# takpad6_2.net
KiCad netlist of a schematic drawn in EAGLE
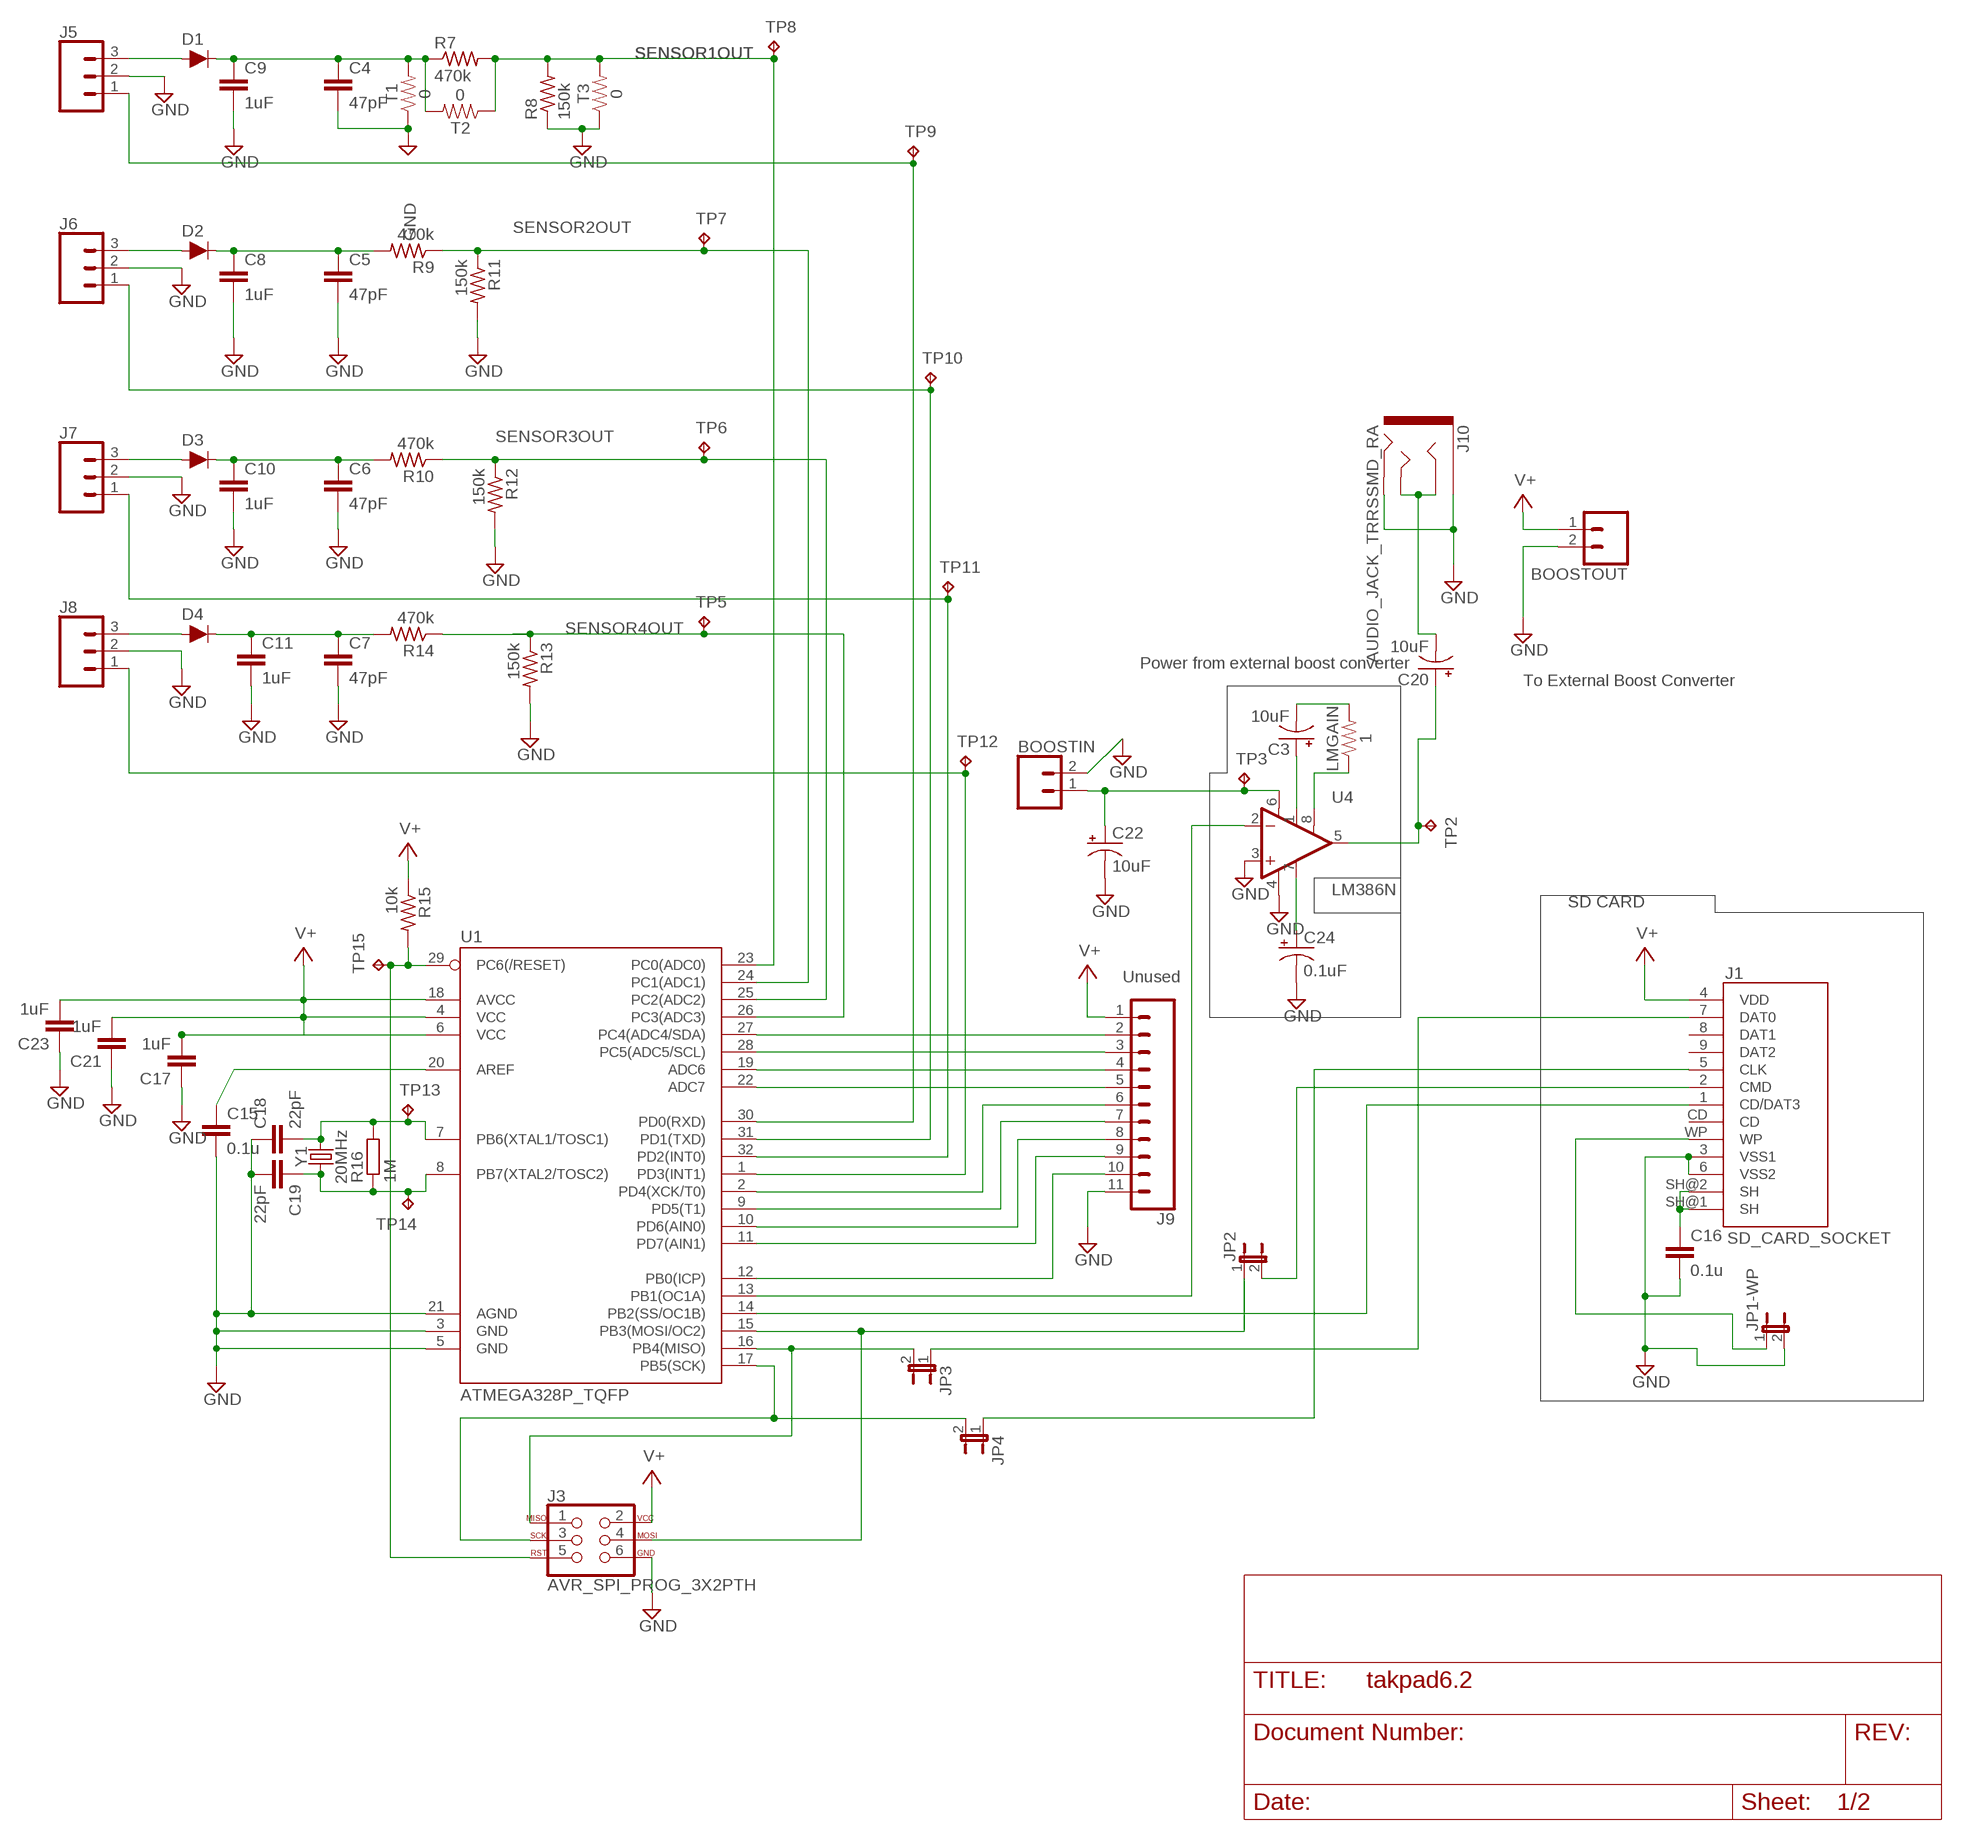
[diagram p0: schematic, sheet 1]
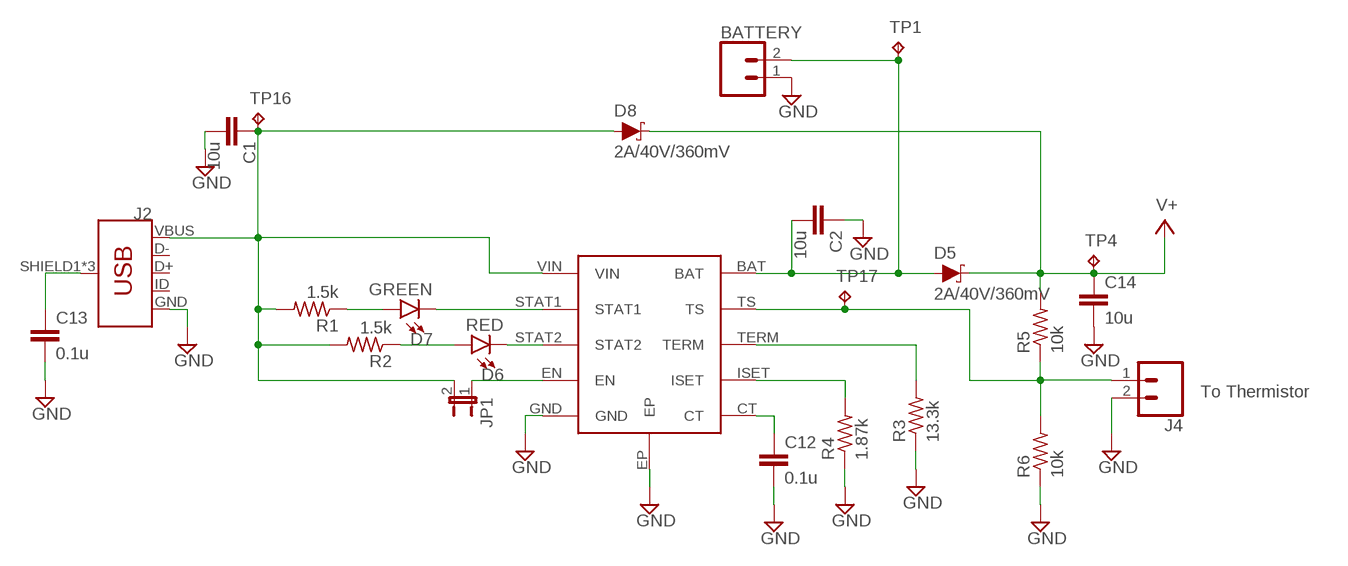
[diagram p1: schematic, sheet 2]

(export (version "E")
  (design (tool "Eeschema 10.0.6"))
  (components
    (comp (ref "BOOSTIN")
      (value "CONN_02")
      (footprint "eagle-import:1X02")
      (libsource (lib "eagle-import") (part "CONN_02"))
    )
    (comp (ref "BOOSTOUT")
      (value "CONN_02")
      (footprint "eagle-import:1X02")
      (libsource (lib "eagle-import") (part "CONN_02"))
    )
    (comp (ref "C3")
      (value "10uF")
      (footprint "eagle-import:CPOL-RADIAL-2.5MM-5MM-KIT")
      (libsource (lib "eagle-import") (part "10UF-POLAR-RADIAL-2.5MM-KIT-25V-20%"))
    )
    (comp (ref "C4")
      (value "47pF")
      (footprint "eagle-import:0603")
      (libsource (lib "eagle-import") (part "47PF-0603-50V-5%"))
    )
    (comp (ref "C5")
      (value "47pF")
      (footprint "eagle-import:0603")
      (libsource (lib "eagle-import") (part "47PF-0603-50V-5%"))
    )
    (comp (ref "C6")
      (value "47pF")
      (footprint "eagle-import:0603")
      (libsource (lib "eagle-import") (part "47PF-0603-50V-5%"))
    )
    (comp (ref "C7")
      (value "47pF")
      (footprint "eagle-import:0603")
      (libsource (lib "eagle-import") (part "47PF-0603-50V-5%"))
    )
    (comp (ref "C8")
      (value "1uF")
      (footprint "eagle-import:0603")
      (libsource (lib "eagle-import") (part "47PF-0603-50V-5%"))
    )
    (comp (ref "C9")
      (value "1uF")
      (footprint "eagle-import:0603")
      (libsource (lib "eagle-import") (part "47PF-0603-50V-5%"))
    )
    (comp (ref "C10")
      (value "1uF")
      (footprint "eagle-import:0603")
      (libsource (lib "eagle-import") (part "47PF-0603-50V-5%"))
    )
    (comp (ref "C11")
      (value "1uF")
      (footprint "eagle-import:0603")
      (libsource (lib "eagle-import") (part "47PF-0603-50V-5%"))
    )
    (comp (ref "C15")
      (value "0.1u")
      (footprint "eagle-import:C0402")
      (libsource (lib "eagle-import") (part "C-EUC0402"))
    )
    (comp (ref "C16")
      (value "0.1u")
      (footprint "eagle-import:C0402")
      (libsource (lib "eagle-import") (part "C-EUC0402"))
    )
    (comp (ref "C17")
      (value "1uF")
      (footprint "eagle-import:0603")
      (libsource (lib "eagle-import") (part "47PF-0603-50V-5%"))
    )
    (comp (ref "C18")
      (value "22pF")
      (footprint "eagle-import:C0402")
      (libsource (lib "eagle-import") (part "resistor_348_C-EUC0402"))
    )
    (comp (ref "C19")
      (value "22pF")
      (footprint "eagle-import:C0402")
      (libsource (lib "eagle-import") (part "resistor_348_C-EUC0402"))
    )
    (comp (ref "C20")
      (value "10uF")
      (footprint "eagle-import:CPOL-RADIAL-2.5MM-5MM-KIT")
      (libsource (lib "eagle-import") (part "10UF-POLAR-RADIAL-2.5MM-KIT-25V-20%"))
    )
    (comp (ref "C21")
      (value "1uF")
      (footprint "eagle-import:0603")
      (libsource (lib "eagle-import") (part "47PF-0603-50V-5%"))
    )
    (comp (ref "C22")
      (value "10uF")
      (footprint "eagle-import:CPOL-RADIAL-2.5MM-5MM-KIT")
      (libsource (lib "eagle-import") (part "10UF-POLAR-RADIAL-2.5MM-KIT-25V-20%"))
    )
    (comp (ref "C23")
      (value "1uF")
      (footprint "eagle-import:0603")
      (libsource (lib "eagle-import") (part "47PF-0603-50V-5%"))
    )
    (comp (ref "C24")
      (value "0.1uF")
      (footprint "eagle-import:CPOL-RADIAL-2.5MM-5MM-KIT")
      (libsource (lib "eagle-import") (part "10UF-POLAR-RADIAL-2.5MM-KIT-25V-20%"))
    )
    (comp (ref "D1")
      (value "200mA/100V/1V")
      (footprint "eagle-import:DIODE-1N4148")
      (libsource (lib "eagle-import") (part "DIODE-1N4148"))
    )
    (comp (ref "D2")
      (value "200mA/100V/1V")
      (footprint "eagle-import:DIODE-1N4148")
      (libsource (lib "eagle-import") (part "DIODE-1N4148"))
    )
    (comp (ref "D3")
      (value "200mA/100V/1V")
      (footprint "eagle-import:DIODE-1N4148")
      (libsource (lib "eagle-import") (part "DIODE-1N4148"))
    )
    (comp (ref "D4")
      (value "200mA/100V/1V")
      (footprint "eagle-import:DIODE-1N4148")
      (libsource (lib "eagle-import") (part "DIODE-1N4148"))
    )
    (comp (ref "J1")
      (value "SD_CARD_SOCKET")
      (footprint "eagle-import:SD")
      (libsource (lib "eagle-import") (part "SD_CARD_SOCKET"))
    )
    (comp (ref "J3")
      (value "AVR_SPI_PROG_3X2PTH")
      (footprint "eagle-import:2X3")
      (libsource (lib "eagle-import") (part "AVR_SPI_PROG_3X2PTH"))
    )
    (comp (ref "J5")
      (value "CONN_03")
      (footprint "eagle-import:1X03")
      (libsource (lib "eagle-import") (part "CONN_03"))
    )
    (comp (ref "J6")
      (value "CONN_03")
      (footprint "eagle-import:1X03")
      (libsource (lib "eagle-import") (part "CONN_03"))
    )
    (comp (ref "J7")
      (value "CONN_03")
      (footprint "eagle-import:1X03")
      (libsource (lib "eagle-import") (part "CONN_03"))
    )
    (comp (ref "J8")
      (value "CONN_03")
      (footprint "eagle-import:1X03")
      (libsource (lib "eagle-import") (part "CONN_03"))
    )
    (comp (ref "J9")
      (value "CONN_11")
      (footprint "eagle-import:1X11")
      (libsource (lib "eagle-import") (part "CONN_11"))
    )
    (comp (ref "J10")
      (value "AUDIO_JACK_TRRSSMD_RA")
      (footprint "eagle-import:AUDIO_JACK_3.5MM_TRRS_SMD_RA")
      (libsource (lib "eagle-import") (part "AUDIO_JACK_TRRSSMD_RA"))
    )
    (comp (ref "JP1-WP")
      (value "JUMPER-2PTH")
      (footprint "eagle-import:1X02")
      (libsource (lib "eagle-import") (part "JUMPER-2PTH"))
    )
    (comp (ref "JP2")
      (value "JUMPER-2PTH")
      (footprint "eagle-import:1X02")
      (libsource (lib "eagle-import") (part "JUMPER-2PTH"))
    )
    (comp (ref "JP3")
      (value "JUMPER-2PTH")
      (footprint "eagle-import:1X02")
      (libsource (lib "eagle-import") (part "JUMPER-2PTH"))
    )
    (comp (ref "JP4")
      (value "JUMPER-2PTH")
      (footprint "eagle-import:1X02")
      (libsource (lib "eagle-import") (part "JUMPER-2PTH"))
    )
    (comp (ref "LMGAIN")
      (value "1")
      (footprint "eagle-import:0603")
      (libsource (lib "eagle-import") (part "1OHM-0603-1/10W-1%"))
    )
    (comp (ref "R7")
      (value "470k")
      (footprint "eagle-import:M1206")
      (libsource (lib "eagle-import") (part "R-US_M1206"))
    )
    (comp (ref "R8")
      (value "150k")
      (footprint "eagle-import:M1206")
      (libsource (lib "eagle-import") (part "R-US_M1206"))
    )
    (comp (ref "R9")
      (value "470k")
      (footprint "eagle-import:M1206")
      (libsource (lib "eagle-import") (part "R-US_M1206"))
    )
    (comp (ref "R10")
      (value "470k")
      (footprint "eagle-import:M1206")
      (libsource (lib "eagle-import") (part "R-US_M1206"))
    )
    (comp (ref "R11")
      (value "150k")
      (footprint "eagle-import:M1206")
      (libsource (lib "eagle-import") (part "R-US_M1206"))
    )
    (comp (ref "R12")
      (value "150k")
      (footprint "eagle-import:M1206")
      (libsource (lib "eagle-import") (part "R-US_M1206"))
    )
    (comp (ref "R13")
      (value "150k")
      (footprint "eagle-import:M1206")
      (libsource (lib "eagle-import") (part "R-US_M1206"))
    )
    (comp (ref "R14")
      (value "470k")
      (footprint "eagle-import:M1206")
      (libsource (lib "eagle-import") (part "R-US_M1206"))
    )
    (comp (ref "R15")
      (value "10k")
      (footprint "eagle-import:M1206")
      (libsource (lib "eagle-import") (part "R-US_M1206"))
    )
    (comp (ref "R16")
      (value "1M")
      (footprint "eagle-import:R0402")
      (libsource (lib "eagle-import") (part "R-EU_R0402"))
    )
    (comp (ref "T1")
      (value "0")
      (footprint "eagle-import:AXIAL-0.3")
      (libsource (lib "eagle-import") (part "1KOHM-HORIZ-1/4W-1%"))
    )
    (comp (ref "T2")
      (value "0")
      (footprint "eagle-import:AXIAL-0.3")
      (libsource (lib "eagle-import") (part "1KOHM-HORIZ-1/4W-1%"))
    )
    (comp (ref "T3")
      (value "0")
      (footprint "eagle-import:AXIAL-0.3")
      (libsource (lib "eagle-import") (part "1KOHM-HORIZ-1/4W-1%"))
    )
    (comp (ref "TP2")
      (value "TPB1,27")
      (footprint "eagle-import:B1,27")
      (libsource (lib "eagle-import") (part "TPB1,27"))
    )
    (comp (ref "TP3")
      (value "TPB1,27")
      (footprint "eagle-import:B1,27")
      (libsource (lib "eagle-import") (part "TPB1,27"))
    )
    (comp (ref "TP5")
      (value "TPB1,27")
      (footprint "eagle-import:B1,27")
      (libsource (lib "eagle-import") (part "TPB1,27"))
    )
    (comp (ref "TP6")
      (value "TPB1,27")
      (footprint "eagle-import:B1,27")
      (libsource (lib "eagle-import") (part "TPB1,27"))
    )
    (comp (ref "TP7")
      (value "TPB1,27")
      (footprint "eagle-import:B1,27")
      (libsource (lib "eagle-import") (part "TPB1,27"))
    )
    (comp (ref "TP8")
      (value "TPB1,27")
      (footprint "eagle-import:B1,27")
      (libsource (lib "eagle-import") (part "TPB1,27"))
    )
    (comp (ref "TP9")
      (value "TPB1,27")
      (footprint "eagle-import:B1,27")
      (libsource (lib "eagle-import") (part "TPB1,27"))
    )
    (comp (ref "TP10")
      (value "TPB1,27")
      (footprint "eagle-import:B1,27")
      (libsource (lib "eagle-import") (part "TPB1,27"))
    )
    (comp (ref "TP11")
      (value "TPB1,27")
      (footprint "eagle-import:B1,27")
      (libsource (lib "eagle-import") (part "TPB1,27"))
    )
    (comp (ref "TP12")
      (value "TPB1,27")
      (footprint "eagle-import:B1,27")
      (libsource (lib "eagle-import") (part "TPB1,27"))
    )
    (comp (ref "TP13")
      (value "TPB1,27")
      (footprint "eagle-import:B1,27")
      (libsource (lib "eagle-import") (part "TPB1,27"))
    )
    (comp (ref "TP14")
      (value "TPB1,27")
      (footprint "eagle-import:B1,27")
      (libsource (lib "eagle-import") (part "TPB1,27"))
    )
    (comp (ref "TP15")
      (value "TPB1,27")
      (footprint "eagle-import:B1,27")
      (libsource (lib "eagle-import") (part "TPB1,27"))
    )
    (comp (ref "U1")
      (value "ATMEGA328P_TQFP")
      (footprint "eagle-import:TQFP32-08")
      (libsource (lib "eagle-import") (part "ATMEGA328P_TQFP"))
    )
    (comp (ref "U4")
      (value "LM386N")
      (footprint "eagle-import:DIP08")
      (libsource (lib "eagle-import") (part "LM386"))
    )
    (comp (ref "Y1")
      (value "20MHz")
      (footprint "eagle-import:HC49US")
      (libsource (lib "eagle-import") (part "CRYSTAL-16MHZPTH-HC49US"))
    )
    (comp (ref "BATTERY")
      (value "CONN_02")
      (footprint "eagle-import:1X02")
      (libsource (lib "eagle-import") (part "CONN_02"))
    )
    (comp (ref "C1")
      (value "10u")
      (footprint "eagle-import:C0402")
      (libsource (lib "eagle-import") (part "C-EUC0402"))
    )
    (comp (ref "C2")
      (value "10u")
      (footprint "eagle-import:C0402")
      (libsource (lib "eagle-import") (part "C-EUC0402"))
    )
    (comp (ref "C12")
      (value "0.1u")
      (footprint "eagle-import:C0402")
      (libsource (lib "eagle-import") (part "C-EUC0402"))
    )
    (comp (ref "C13")
      (value "0.1u")
      (footprint "eagle-import:C0402")
      (libsource (lib "eagle-import") (part "C-EUC0402"))
    )
    (comp (ref "C14")
      (value "10u")
      (footprint "eagle-import:C0402")
      (libsource (lib "eagle-import") (part "C-EUC0402"))
    )
    (comp (ref "D5")
      (value "2A/40V/360mV")
      (footprint "eagle-import:SMA-DIODE")
      (libsource (lib "eagle-import") (part "DIODE-SCHOTTKY-B340A"))
    )
    (comp (ref "D6")
      (value "RED")
      (footprint "eagle-import:LED-1206")
      (libsource (lib "eagle-import") (part "LED-RED1206"))
    )
    (comp (ref "D7")
      (value "GREEN")
      (footprint "eagle-import:LED-1206")
      (libsource (lib "eagle-import") (part "LED-GREEN1206"))
    )
    (comp (ref "D8")
      (value "2A/40V/360mV")
      (footprint "eagle-import:SMA-DIODE")
      (libsource (lib "eagle-import") (part "DIODE-SCHOTTKY-B340A"))
    )
    (comp (ref "J2")
      (value "USB_MICRO-BREDUCED_PASTE")
      (footprint "eagle-import:USB-B-MICRO-SMD_RED_PASTE")
      (libsource (lib "eagle-import") (part "USB_MICRO-BREDUCED_PASTE"))
    )
    (comp (ref "J4")
      (value "CONN_02")
      (footprint "eagle-import:1X02")
      (libsource (lib "eagle-import") (part "CONN_02"))
    )
    (comp (ref "JP1")
      (value "JUMPER-2PTH")
      (footprint "eagle-import:1X02")
      (libsource (lib "eagle-import") (part "JUMPER-2PTH"))
    )
    (comp (ref "R1")
      (value "1.5k")
      (footprint "eagle-import:M1206")
      (libsource (lib "eagle-import") (part "R-US_M1206"))
    )
    (comp (ref "R2")
      (value "1.5k")
      (footprint "eagle-import:M1206")
      (libsource (lib "eagle-import") (part "R-US_M1206"))
    )
    (comp (ref "R3")
      (value "13.3k")
      (footprint "eagle-import:M1206")
      (libsource (lib "eagle-import") (part "R-US_M1206"))
    )
    (comp (ref "R4")
      (value "1.87k")
      (footprint "eagle-import:M1206")
      (libsource (lib "eagle-import") (part "R-US_M1206"))
    )
    (comp (ref "R5")
      (value "10k")
      (footprint "eagle-import:M1206")
      (libsource (lib "eagle-import") (part "R-US_M1206"))
    )
    (comp (ref "R6")
      (value "10k")
      (footprint "eagle-import:M1206")
      (libsource (lib "eagle-import") (part "R-US_M1206"))
    )
    (comp (ref "TP1")
      (value "TPB1,27")
      (footprint "eagle-import:B1,27")
      (libsource (lib "eagle-import") (part "TPB1,27"))
    )
    (comp (ref "TP4")
      (value "TPB1,27")
      (footprint "eagle-import:B1,27")
      (libsource (lib "eagle-import") (part "TPB1,27"))
    )
    (comp (ref "TP16")
      (value "TPB1,27")
      (footprint "eagle-import:B1,27")
      (libsource (lib "eagle-import") (part "TPB1,27"))
    )
    (comp (ref "TP17")
      (value "TPB1,27")
      (footprint "eagle-import:B1,27")
      (libsource (lib "eagle-import") (part "TPB1,27"))
    )
    (comp (ref "U$1")
      (value "AAT3693")
      (footprint "eagle-import:IDH-AA-T1")
      (libsource (lib "eagle-import") (part "AAT3693"))
    )
  )
  (nets
    (net (code "1") (name "GND") (class "Default")
      (node (ref "BATTERY") (pin "1") (pinfunction "1_1") (pintype "passive"))
      (node (ref "BOOSTIN") (pin "2") (pinfunction "2_2") (pintype "passive"))
      (node (ref "BOOSTOUT") (pin "2") (pinfunction "2_2") (pintype "passive"))
      (node (ref "C1") (pin "2") (pinfunction "2_2") (pintype "passive"))
      (node (ref "C10") (pin "2") (pinfunction "2_2") (pintype "passive"))
      (node (ref "C11") (pin "2") (pinfunction "2_2") (pintype "passive"))
      (node (ref "C12") (pin "2") (pinfunction "2_2") (pintype "passive"))
      (node (ref "C13") (pin "2") (pinfunction "2_2") (pintype "passive"))
      (node (ref "C14") (pin "2") (pinfunction "2_2") (pintype "passive"))
      (node (ref "C15") (pin "2") (pinfunction "2_2") (pintype "passive"))
      (node (ref "C16") (pin "2") (pinfunction "2_2") (pintype "passive"))
      (node (ref "C17") (pin "1") (pinfunction "1_1") (pintype "passive"))
      (node (ref "C18") (pin "1") (pinfunction "1_1") (pintype "passive"))
      (node (ref "C19") (pin "2") (pinfunction "2_2") (pintype "passive"))
      (node (ref "C2") (pin "1") (pinfunction "1_1") (pintype "passive"))
      (node (ref "C21") (pin "1") (pinfunction "1_1") (pintype "passive"))
      (node (ref "C22") (pin "2") (pinfunction "-_2") (pintype "passive"))
      (node (ref "C23") (pin "1") (pinfunction "1_1") (pintype "passive"))
      (node (ref "C24") (pin "2") (pinfunction "-_2") (pintype "passive"))
      (node (ref "C4") (pin "2") (pinfunction "2_2") (pintype "passive"))
      (node (ref "C5") (pin "2") (pinfunction "2_2") (pintype "passive"))
      (node (ref "C6") (pin "2") (pinfunction "2_2") (pintype "passive"))
      (node (ref "C7") (pin "2") (pinfunction "2_2") (pintype "passive"))
      (node (ref "C8") (pin "2") (pinfunction "2_2") (pintype "passive"))
      (node (ref "C9") (pin "2") (pinfunction "2_2") (pintype "passive"))
      (node (ref "J1") (pin "3") (pinfunction "VSS1_3") (pintype "power_in"))
      (node (ref "J1") (pin "6") (pinfunction "VSS2_6") (pintype "power_in"))
      (node (ref "J10") (pin "EARTH") (pinfunction "EARTH_EARTH") (pintype "bidirectional"))
      (node (ref "J10") (pin "RING2") (pinfunction "RING2_RING2") (pintype "bidirectional"))
      (node (ref "J2") (pin "GND") (pinfunction "GND_GND") (pintype "power_in"))
      (node (ref "J3") (pin "6") (pinfunction "6_6") (pintype "passive"))
      (node (ref "J4") (pin "2") (pinfunction "2_2") (pintype "passive"))
      (node (ref "J5") (pin "2") (pinfunction "2_2") (pintype "passive"))
      (node (ref "J6") (pin "2") (pinfunction "2_2") (pintype "passive"))
      (node (ref "J7") (pin "2") (pinfunction "2_2") (pintype "passive"))
      (node (ref "J8") (pin "2") (pinfunction "2_2") (pintype "passive"))
      (node (ref "J9") (pin "11") (pinfunction "11_11") (pintype "passive"))
      (node (ref "JP1-WP") (pin "2") (pinfunction "2_2") (pintype "passive"))
      (node (ref "R11") (pin "2") (pinfunction "2_2") (pintype "passive"))
      (node (ref "R12") (pin "2") (pinfunction "2_2") (pintype "passive"))
      (node (ref "R13") (pin "2") (pinfunction "2_2") (pintype "passive"))
      (node (ref "R3") (pin "1") (pinfunction "1_1") (pintype "passive"))
      (node (ref "R4") (pin "1") (pinfunction "1_1") (pintype "passive"))
      (node (ref "R6") (pin "1") (pinfunction "1_1") (pintype "passive"))
      (node (ref "R8") (pin "1") (pinfunction "1_1") (pintype "passive"))
      (node (ref "T1") (pin "P$1") (pinfunction "1_P$1") (pintype "passive"))
      (node (ref "T3") (pin "P$1") (pinfunction "1_P$1") (pintype "passive"))
      (node (ref "U$1") (pin "EP") (pinfunction "EP_EP") (pintype "bidirectional"))
      (node (ref "U$1") (pin "GND") (pinfunction "GND_GND") (pintype "bidirectional"))
      (node (ref "U1") (pin "21") (pinfunction "AGND_21") (pintype "bidirectional"))
      (node (ref "U1") (pin "3") (pinfunction "GND_3") (pintype "bidirectional"))
      (node (ref "U1") (pin "5") (pinfunction "GND_5") (pintype "bidirectional"))
      (node (ref "U4") (pin "3") (pinfunction "+IN_3") (pintype "input"))
      (node (ref "U4") (pin "4") (pinfunction "V-_4") (pintype "power_in"))
    )
    (net (code "2") (name "Net-(BATTERY-Pad2)") (class "Default")
      (node (ref "BATTERY") (pin "2") (pinfunction "2_2") (pintype "passive"))
      (node (ref "C2") (pin "2") (pinfunction "2_2") (pintype "passive"))
      (node (ref "D5") (pin "A") (pinfunction "A_A") (pintype "passive"))
      (node (ref "TP1") (pin "TP") (pinfunction "TP_TP") (pintype "input"))
      (node (ref "U$1") (pin "BAT") (pinfunction "BAT_BAT") (pintype "bidirectional"))
    )
    (net (code "3") (name "Net-(C1-Pad1)") (class "Default")
      (node (ref "C1") (pin "1") (pinfunction "1_1") (pintype "passive"))
      (node (ref "D8") (pin "A") (pinfunction "A_A") (pintype "passive"))
      (node (ref "J2") (pin "VBUS") (pinfunction "VBUS_VBUS") (pintype "power_in"))
      (node (ref "JP1") (pin "2") (pinfunction "2_2") (pintype "passive"))
      (node (ref "R1") (pin "2") (pinfunction "2_2") (pintype "passive"))
      (node (ref "R2") (pin "2") (pinfunction "2_2") (pintype "passive"))
      (node (ref "TP16") (pin "TP") (pinfunction "TP_TP") (pintype "input"))
      (node (ref "U$1") (pin "VIN") (pinfunction "VIN_VIN") (pintype "bidirectional"))
    )
    (net (code "4") (name "Net-(C3-+)") (class "Default")
      (node (ref "C3") (pin "1") (pinfunction "+_1") (pintype "passive"))
      (node (ref "U4") (pin "1") (pinfunction "GAIN_1") (pintype "bidirectional"))
    )
    (net (code "5") (name "Net-(C3--)") (class "Default")
      (node (ref "C3") (pin "2") (pinfunction "-_2") (pintype "passive"))
      (node (ref "LMGAIN") (pin "2") (pinfunction "2_2") (pintype "passive"))
    )
    (net (code "6") (name "Net-(C5-Pad1)") (class "Default")
      (node (ref "C5") (pin "1") (pinfunction "1_1") (pintype "passive"))
      (node (ref "C8") (pin "1") (pinfunction "1_1") (pintype "passive"))
      (node (ref "D2") (pin "C") (pinfunction "C_C") (pintype "passive"))
      (node (ref "R9") (pin "2") (pinfunction "2_2") (pintype "passive"))
    )
    (net (code "7") (name "Net-(C10-Pad1)") (class "Default")
      (node (ref "C10") (pin "1") (pinfunction "1_1") (pintype "passive"))
      (node (ref "C6") (pin "1") (pinfunction "1_1") (pintype "passive"))
      (node (ref "D3") (pin "C") (pinfunction "C_C") (pintype "passive"))
      (node (ref "R10") (pin "2") (pinfunction "2_2") (pintype "passive"))
    )
    (net (code "8") (name "Net-(C11-Pad1)") (class "Default")
      (node (ref "C11") (pin "1") (pinfunction "1_1") (pintype "passive"))
      (node (ref "C7") (pin "1") (pinfunction "1_1") (pintype "passive"))
      (node (ref "D4") (pin "C") (pinfunction "C_C") (pintype "passive"))
      (node (ref "R14") (pin "2") (pinfunction "2_2") (pintype "passive"))
    )
    (net (code "9") (name "Net-(C12-Pad1)") (class "Default")
      (node (ref "C12") (pin "1") (pinfunction "1_1") (pintype "passive"))
      (node (ref "U$1") (pin "CT") (pinfunction "CT_CT") (pintype "bidirectional"))
    )
    (net (code "10") (name "Net-(C13-Pad1)") (class "Default")
      (node (ref "C13") (pin "1") (pinfunction "1_1") (pintype "passive"))
      (node (ref "J2") (pin "SHIELD1") (pinfunction "SHIELD_SHIELD1") (pintype "bidirectional"))
      (node (ref "J2") (pin "SHIELD2") (pinfunction "SHIELD_SHIELD2") (pintype "bidirectional"))
      (node (ref "J2") (pin "SHIELD3") (pinfunction "SHIELD_SHIELD3") (pintype "bidirectional"))
    )
    (net (code "11") (name "Net-(C16-Pad1)") (class "Default")
      (node (ref "C16") (pin "1") (pinfunction "1_1") (pintype "passive"))
      (node (ref "J1") (pin "SH@1") (pinfunction "SH_SH@1") (pintype "bidirectional"))
      (node (ref "J1") (pin "SH@2") (pinfunction "SH_SH@2") (pintype "bidirectional"))
    )
    (net (code "12") (name "Net-(C20-+)") (class "Default")
      (node (ref "C20") (pin "1") (pinfunction "+_1") (pintype "passive"))
      (node (ref "TP2") (pin "TP") (pinfunction "TP_TP") (pintype "input"))
      (node (ref "U4") (pin "5") (pinfunction "OUT_5") (pintype "output"))
    )
    (net (code "13") (name "Net-(C20--)") (class "Default")
      (node (ref "C20") (pin "2") (pinfunction "-_2") (pintype "passive"))
      (node (ref "J10") (pin "RING1") (pinfunction "RING1_RING1") (pintype "bidirectional"))
      (node (ref "J10") (pin "TIP") (pinfunction "TIP_TIP") (pintype "bidirectional"))
    )
    (net (code "14") (name "Net-(C22-+)") (class "Default")
      (node (ref "BOOSTIN") (pin "1") (pinfunction "1_1") (pintype "passive"))
      (node (ref "C22") (pin "1") (pinfunction "+_1") (pintype "passive"))
      (node (ref "TP3") (pin "TP") (pinfunction "TP_TP") (pintype "input"))
      (node (ref "U4") (pin "6") (pinfunction "V+_6") (pintype "power_in"))
    )
    (net (code "15") (name "Net-(C24-+)") (class "Default")
      (node (ref "C24") (pin "1") (pinfunction "+_1") (pintype "passive"))
      (node (ref "U4") (pin "7") (pinfunction "BP_7") (pintype "bidirectional"))
    )
    (net (code "16") (name "Net-(D1-PadA)") (class "Default")
      (node (ref "D1") (pin "A") (pinfunction "A_A") (pintype "passive"))
      (node (ref "J5") (pin "3") (pinfunction "3_3") (pintype "passive"))
    )
    (net (code "17") (name "Net-(D2-PadA)") (class "Default")
      (node (ref "D2") (pin "A") (pinfunction "A_A") (pintype "passive"))
      (node (ref "J6") (pin "3") (pinfunction "3_3") (pintype "passive"))
    )
    (net (code "18") (name "Net-(D3-PadA)") (class "Default")
      (node (ref "D3") (pin "A") (pinfunction "A_A") (pintype "passive"))
      (node (ref "J7") (pin "3") (pinfunction "3_3") (pintype "passive"))
    )
    (net (code "19") (name "Net-(D4-PadA)") (class "Default")
      (node (ref "D4") (pin "A") (pinfunction "A_A") (pintype "passive"))
      (node (ref "J8") (pin "3") (pinfunction "3_3") (pintype "passive"))
    )
    (net (code "20") (name "Net-(D6-PadA)") (class "Default")
      (node (ref "D6") (pin "A") (pinfunction "A_A") (pintype "passive"))
      (node (ref "R2") (pin "1") (pinfunction "1_1") (pintype "passive"))
    )
    (net (code "21") (name "Net-(D6-PadC)") (class "Default")
      (node (ref "D6") (pin "C") (pinfunction "C_C") (pintype "passive"))
      (node (ref "U$1") (pin "STAT2") (pinfunction "STAT2_STAT2") (pintype "bidirectional"))
    )
    (net (code "22") (name "Net-(D7-PadA)") (class "Default")
      (node (ref "D7") (pin "A") (pinfunction "A_A") (pintype "passive"))
      (node (ref "R1") (pin "1") (pinfunction "1_1") (pintype "passive"))
    )
    (net (code "23") (name "Net-(D7-PadC)") (class "Default")
      (node (ref "D7") (pin "C") (pinfunction "C_C") (pintype "passive"))
      (node (ref "U$1") (pin "STAT1") (pinfunction "STAT1_STAT1") (pintype "bidirectional"))
    )
    (net (code "24") (name "Net-(J1-CD{slash}DAT3)") (class "Default")
      (node (ref "J1") (pin "1") (pinfunction "CD/DAT3_1") (pintype "bidirectional"))
      (node (ref "U1") (pin "14") (pinfunction "PB2(SS/OC1B)_14") (pintype "bidirectional"))
    )
    (net (code "25") (name "Net-(J1-CLK)") (class "Default")
      (node (ref "J1") (pin "5") (pinfunction "CLK_5") (pintype "bidirectional"))
      (node (ref "JP4") (pin "1") (pinfunction "1_1") (pintype "passive"))
    )
    (net (code "26") (name "Net-(J1-CMD)") (class "Default")
      (node (ref "J1") (pin "2") (pinfunction "CMD_2") (pintype "bidirectional"))
      (node (ref "JP2") (pin "2") (pinfunction "2_2") (pintype "passive"))
    )
    (net (code "27") (name "Net-(J1-DAT0)") (class "Default")
      (node (ref "J1") (pin "7") (pinfunction "DAT0_7") (pintype "bidirectional"))
      (node (ref "JP3") (pin "1") (pinfunction "1_1") (pintype "passive"))
    )
    (net (code "28") (name "Net-(J1-PadWP)") (class "Default")
      (node (ref "J1") (pin "WP") (pinfunction "WP_WP") (pintype "bidirectional"))
      (node (ref "JP1-WP") (pin "1") (pinfunction "1_1") (pintype "passive"))
    )
    (net (code "29") (name "Net-(J4-Pad1)") (class "Default")
      (node (ref "J4") (pin "1") (pinfunction "1_1") (pintype "passive"))
      (node (ref "R5") (pin "1") (pinfunction "1_1") (pintype "passive"))
      (node (ref "R6") (pin "2") (pinfunction "2_2") (pintype "passive"))
      (node (ref "TP17") (pin "TP") (pinfunction "TP_TP") (pintype "input"))
      (node (ref "U$1") (pin "TS") (pinfunction "TS_TS") (pintype "bidirectional"))
    )
    (net (code "30") (name "Net-(JP1-Pad1)") (class "Default")
      (node (ref "JP1") (pin "1") (pinfunction "1_1") (pintype "passive"))
      (node (ref "U$1") (pin "EN") (pinfunction "EN_EN") (pintype "bidirectional"))
    )
    (net (code "31") (name "Net-(LMGAIN-Pad1)") (class "Default")
      (node (ref "LMGAIN") (pin "1") (pinfunction "1_1") (pintype "passive"))
      (node (ref "U4") (pin "8") (pinfunction "GAIN_8") (pintype "bidirectional"))
    )
    (net (code "32") (name "Net-(R3-Pad2)") (class "Default")
      (node (ref "R3") (pin "2") (pinfunction "2_2") (pintype "passive"))
      (node (ref "U$1") (pin "TERM") (pinfunction "TERM_TERM") (pintype "bidirectional"))
    )
    (net (code "33") (name "Net-(R4-Pad2)") (class "Default")
      (node (ref "R4") (pin "2") (pinfunction "2_2") (pintype "passive"))
      (node (ref "U$1") (pin "ISET") (pinfunction "ISET_ISET") (pintype "bidirectional"))
    )
    (net (code "34") (name "Net-(T1-2)") (class "Default")
      (node (ref "C4") (pin "1") (pinfunction "1_1") (pintype "passive"))
      (node (ref "C9") (pin "1") (pinfunction "1_1") (pintype "passive"))
      (node (ref "D1") (pin "C") (pinfunction "C_C") (pintype "passive"))
      (node (ref "R7") (pin "1") (pinfunction "1_1") (pintype "passive"))
      (node (ref "T1") (pin "P$2") (pinfunction "2_P$2") (pintype "passive"))
      (node (ref "T2") (pin "P$2") (pinfunction "2_P$2") (pintype "passive"))
    )
    (net (code "35") (name "Net-(U1-ADC6)") (class "Default")
      (node (ref "J9") (pin "4") (pinfunction "4_4") (pintype "passive"))
      (node (ref "U1") (pin "19") (pinfunction "ADC6_19") (pintype "bidirectional"))
    )
    (net (code "36") (name "Net-(U1-ADC7)") (class "Default")
      (node (ref "J9") (pin "5") (pinfunction "5_5") (pintype "passive"))
      (node (ref "U1") (pin "22") (pinfunction "ADC7_22") (pintype "bidirectional"))
    )
    (net (code "37") (name "Net-(U1-AREF)") (class "Default")
      (node (ref "C15") (pin "1") (pinfunction "1_1") (pintype "passive"))
      (node (ref "U1") (pin "20") (pinfunction "AREF_20") (pintype "bidirectional"))
    )
    (net (code "38") (name "Net-(U1-PB0(ICP))") (class "Default")
      (node (ref "J9") (pin "10") (pinfunction "10_10") (pintype "passive"))
      (node (ref "U1") (pin "12") (pinfunction "PB0(ICP)_12") (pintype "bidirectional"))
    )
    (net (code "39") (name "Net-(U1-PB1(OC1A))") (class "Default")
      (node (ref "U1") (pin "13") (pinfunction "PB1(OC1A)_13") (pintype "bidirectional"))
      (node (ref "U4") (pin "2") (pinfunction "-IN_2") (pintype "input"))
    )
    (net (code "40") (name "Net-(U1-PB3(MOSI{slash}OC2))") (class "Default")
      (node (ref "J3") (pin "4") (pinfunction "4_4") (pintype "passive"))
      (node (ref "JP2") (pin "1") (pinfunction "1_1") (pintype "passive"))
      (node (ref "U1") (pin "15") (pinfunction "PB3(MOSI/OC2)_15") (pintype "bidirectional"))
    )
    (net (code "41") (name "Net-(U1-PB4(MISO))") (class "Default")
      (node (ref "J3") (pin "1") (pinfunction "1_1") (pintype "passive"))
      (node (ref "JP3") (pin "2") (pinfunction "2_2") (pintype "passive"))
      (node (ref "U1") (pin "16") (pinfunction "PB4(MISO)_16") (pintype "bidirectional"))
    )
    (net (code "42") (name "Net-(U1-PB5(SCK))") (class "Default")
      (node (ref "J3") (pin "3") (pinfunction "3_3") (pintype "passive"))
      (node (ref "JP4") (pin "2") (pinfunction "2_2") (pintype "passive"))
      (node (ref "U1") (pin "17") (pinfunction "PB5(SCK)_17") (pintype "bidirectional"))
    )
    (net (code "43") (name "Net-(U1-PB6(XTAL1{slash}TOSC1))") (class "Default")
      (node (ref "C18") (pin "2") (pinfunction "2_2") (pintype "passive"))
      (node (ref "R16") (pin "2") (pinfunction "2_2") (pintype "passive"))
      (node (ref "TP13") (pin "TP") (pinfunction "TP_TP") (pintype "input"))
      (node (ref "U1") (pin "7") (pinfunction "PB6(XTAL1/TOSC1)_7") (pintype "bidirectional"))
      (node (ref "Y1") (pin "2") (pinfunction "2_2") (pintype "passive"))
    )
    (net (code "44") (name "Net-(U1-PB7(XTAL2{slash}TOSC2))") (class "Default")
      (node (ref "C19") (pin "1") (pinfunction "1_1") (pintype "passive"))
      (node (ref "R16") (pin "1") (pinfunction "1_1") (pintype "passive"))
      (node (ref "TP14") (pin "TP") (pinfunction "TP_TP") (pintype "input"))
      (node (ref "U1") (pin "8") (pinfunction "PB7(XTAL2/TOSC2)_8") (pintype "bidirectional"))
      (node (ref "Y1") (pin "1") (pinfunction "1_1") (pintype "passive"))
    )
    (net (code "45") (name "Net-(U1-PC4(ADC4{slash}SDA))") (class "Default")
      (node (ref "J9") (pin "2") (pinfunction "2_2") (pintype "passive"))
      (node (ref "U1") (pin "27") (pinfunction "PC4(ADC4/SDA)_27") (pintype "bidirectional"))
    )
    (net (code "46") (name "Net-(U1-PC5(ADC5{slash}SCL))") (class "Default")
      (node (ref "J9") (pin "3") (pinfunction "3_3") (pintype "passive"))
      (node (ref "U1") (pin "28") (pinfunction "PC5(ADC5/SCL)_28") (pintype "bidirectional"))
    )
    (net (code "47") (name "Net-(U1-PC6({slash}RESET))") (class "Default")
      (node (ref "J3") (pin "5") (pinfunction "5_5") (pintype "passive"))
      (node (ref "R15") (pin "2") (pinfunction "2_2") (pintype "passive"))
      (node (ref "TP15") (pin "TP") (pinfunction "TP_TP") (pintype "input"))
      (node (ref "U1") (pin "29") (pinfunction "PC6(/RESET)_29") (pintype "bidirectional"))
    )
    (net (code "48") (name "Net-(U1-PD0(RXD))") (class "Default")
      (node (ref "J5") (pin "1") (pinfunction "1_1") (pintype "passive"))
      (node (ref "TP9") (pin "TP") (pinfunction "TP_TP") (pintype "input"))
      (node (ref "U1") (pin "30") (pinfunction "PD0(RXD)_30") (pintype "bidirectional"))
    )
    (net (code "49") (name "Net-(U1-PD1(TXD))") (class "Default")
      (node (ref "J6") (pin "1") (pinfunction "1_1") (pintype "passive"))
      (node (ref "TP10") (pin "TP") (pinfunction "TP_TP") (pintype "input"))
      (node (ref "U1") (pin "31") (pinfunction "PD1(TXD)_31") (pintype "bidirectional"))
    )
    (net (code "50") (name "Net-(U1-PD2(INT0))") (class "Default")
      (node (ref "J7") (pin "1") (pinfunction "1_1") (pintype "passive"))
      (node (ref "TP11") (pin "TP") (pinfunction "TP_TP") (pintype "input"))
      (node (ref "U1") (pin "32") (pinfunction "PD2(INT0)_32") (pintype "bidirectional"))
    )
    (net (code "51") (name "Net-(U1-PD3(INT1))") (class "Default")
      (node (ref "J8") (pin "1") (pinfunction "1_1") (pintype "passive"))
      (node (ref "TP12") (pin "TP") (pinfunction "TP_TP") (pintype "input"))
      (node (ref "U1") (pin "1") (pinfunction "PD3(INT1)_1") (pintype "bidirectional"))
    )
    (net (code "52") (name "Net-(U1-PD4(XCK{slash}T0))") (class "Default")
      (node (ref "J9") (pin "6") (pinfunction "6_6") (pintype "passive"))
      (node (ref "U1") (pin "2") (pinfunction "PD4(XCK/T0)_2") (pintype "bidirectional"))
    )
    (net (code "53") (name "Net-(U1-PD5(T1))") (class "Default")
      (node (ref "J9") (pin "7") (pinfunction "7_7") (pintype "passive"))
      (node (ref "U1") (pin "9") (pinfunction "PD5(T1)_9") (pintype "bidirectional"))
    )
    (net (code "54") (name "Net-(U1-PD6(AIN0))") (class "Default")
      (node (ref "J9") (pin "8") (pinfunction "8_8") (pintype "passive"))
      (node (ref "U1") (pin "10") (pinfunction "PD6(AIN0)_10") (pintype "bidirectional"))
    )
    (net (code "55") (name "Net-(U1-PD7(AIN1))") (class "Default")
      (node (ref "J9") (pin "9") (pinfunction "9_9") (pintype "passive"))
      (node (ref "U1") (pin "11") (pinfunction "PD7(AIN1)_11") (pintype "bidirectional"))
    )
    (net (code "56") (name "SENSOR1OUT") (class "Default")
      (node (ref "R7") (pin "2") (pinfunction "2_2") (pintype "passive"))
      (node (ref "R8") (pin "2") (pinfunction "2_2") (pintype "passive"))
      (node (ref "T2") (pin "P$1") (pinfunction "1_P$1") (pintype "passive"))
      (node (ref "T3") (pin "P$2") (pinfunction "2_P$2") (pintype "passive"))
      (node (ref "TP8") (pin "TP") (pinfunction "TP_TP") (pintype "input"))
      (node (ref "U1") (pin "23") (pinfunction "PC0(ADC0)_23") (pintype "bidirectional"))
    )
    (net (code "57") (name "SENSOR2OUT") (class "Default")
      (node (ref "R11") (pin "1") (pinfunction "1_1") (pintype "passive"))
      (node (ref "R9") (pin "1") (pinfunction "1_1") (pintype "passive"))
      (node (ref "TP7") (pin "TP") (pinfunction "TP_TP") (pintype "input"))
      (node (ref "U1") (pin "24") (pinfunction "PC1(ADC1)_24") (pintype "bidirectional"))
    )
    (net (code "58") (name "SENSOR3OUT") (class "Default")
      (node (ref "R10") (pin "1") (pinfunction "1_1") (pintype "passive"))
      (node (ref "R12") (pin "1") (pinfunction "1_1") (pintype "passive"))
      (node (ref "TP6") (pin "TP") (pinfunction "TP_TP") (pintype "input"))
      (node (ref "U1") (pin "25") (pinfunction "PC2(ADC2)_25") (pintype "bidirectional"))
    )
    (net (code "59") (name "SENSOR4OUT") (class "Default")
      (node (ref "R13") (pin "1") (pinfunction "1_1") (pintype "passive"))
      (node (ref "R14") (pin "1") (pinfunction "1_1") (pintype "passive"))
      (node (ref "TP5") (pin "TP") (pinfunction "TP_TP") (pintype "input"))
      (node (ref "U1") (pin "26") (pinfunction "PC3(ADC3)_26") (pintype "bidirectional"))
    )
    (net (code "60") (name "V+") (class "Default")
      (node (ref "BOOSTOUT") (pin "1") (pinfunction "1_1") (pintype "passive"))
      (node (ref "C14") (pin "1") (pinfunction "1_1") (pintype "passive"))
      (node (ref "C17") (pin "2") (pinfunction "2_2") (pintype "passive"))
      (node (ref "C21") (pin "2") (pinfunction "2_2") (pintype "passive"))
      (node (ref "C23") (pin "2") (pinfunction "2_2") (pintype "passive"))
      (node (ref "D5") (pin "C") (pinfunction "C_C") (pintype "passive"))
      (node (ref "D8") (pin "C") (pinfunction "C_C") (pintype "passive"))
      (node (ref "J1") (pin "4") (pinfunction "VDD_4") (pintype "power_in"))
      (node (ref "J3") (pin "2") (pinfunction "2_2") (pintype "passive"))
      (node (ref "J9") (pin "1") (pinfunction "1_1") (pintype "passive"))
      (node (ref "R15") (pin "1") (pinfunction "1_1") (pintype "passive"))
      (node (ref "R5") (pin "2") (pinfunction "2_2") (pintype "passive"))
      (node (ref "TP4") (pin "TP") (pinfunction "TP_TP") (pintype "input"))
      (node (ref "U1") (pin "18") (pinfunction "AVCC_18") (pintype "bidirectional"))
      (node (ref "U1") (pin "4") (pinfunction "VCC_4") (pintype "bidirectional"))
      (node (ref "U1") (pin "6") (pinfunction "VCC_6") (pintype "bidirectional"))
    )
    (net (code "61") (name "unconnected-(J1-DAT1-Pad8)") (class "Default")
      (node (ref "J1") (pin "8") (pinfunction "DAT1_8") (pintype "bidirectional"))
    )
    (net (code "62") (name "unconnected-(J1-DAT2-Pad9)") (class "Default")
      (node (ref "J1") (pin "9") (pinfunction "DAT2_9") (pintype "bidirectional"))
    )
    (net (code "63") (name "unconnected-(J1-PadCD)") (class "Default")
      (node (ref "J1") (pin "CD") (pinfunction "CD_CD") (pintype "bidirectional"))
    )
    (net (code "64") (name "unconnected-(J2-PadD+)") (class "Default")
      (node (ref "J2") (pin "D+") (pinfunction "D+_D+") (pintype "bidirectional"))
    )
    (net (code "65") (name "unconnected-(J2-PadD-)") (class "Default")
      (node (ref "J2") (pin "D-") (pinfunction "D-_D-") (pintype "bidirectional"))
    )
    (net (code "66") (name "unconnected-(J2-PadID)") (class "Default")
      (node (ref "J2") (pin "ID") (pinfunction "ID_ID") (pintype "bidirectional"))
    )
  )
)
